# MPPT3.net
KiCad netlist of a schematic drawn in EAGLE
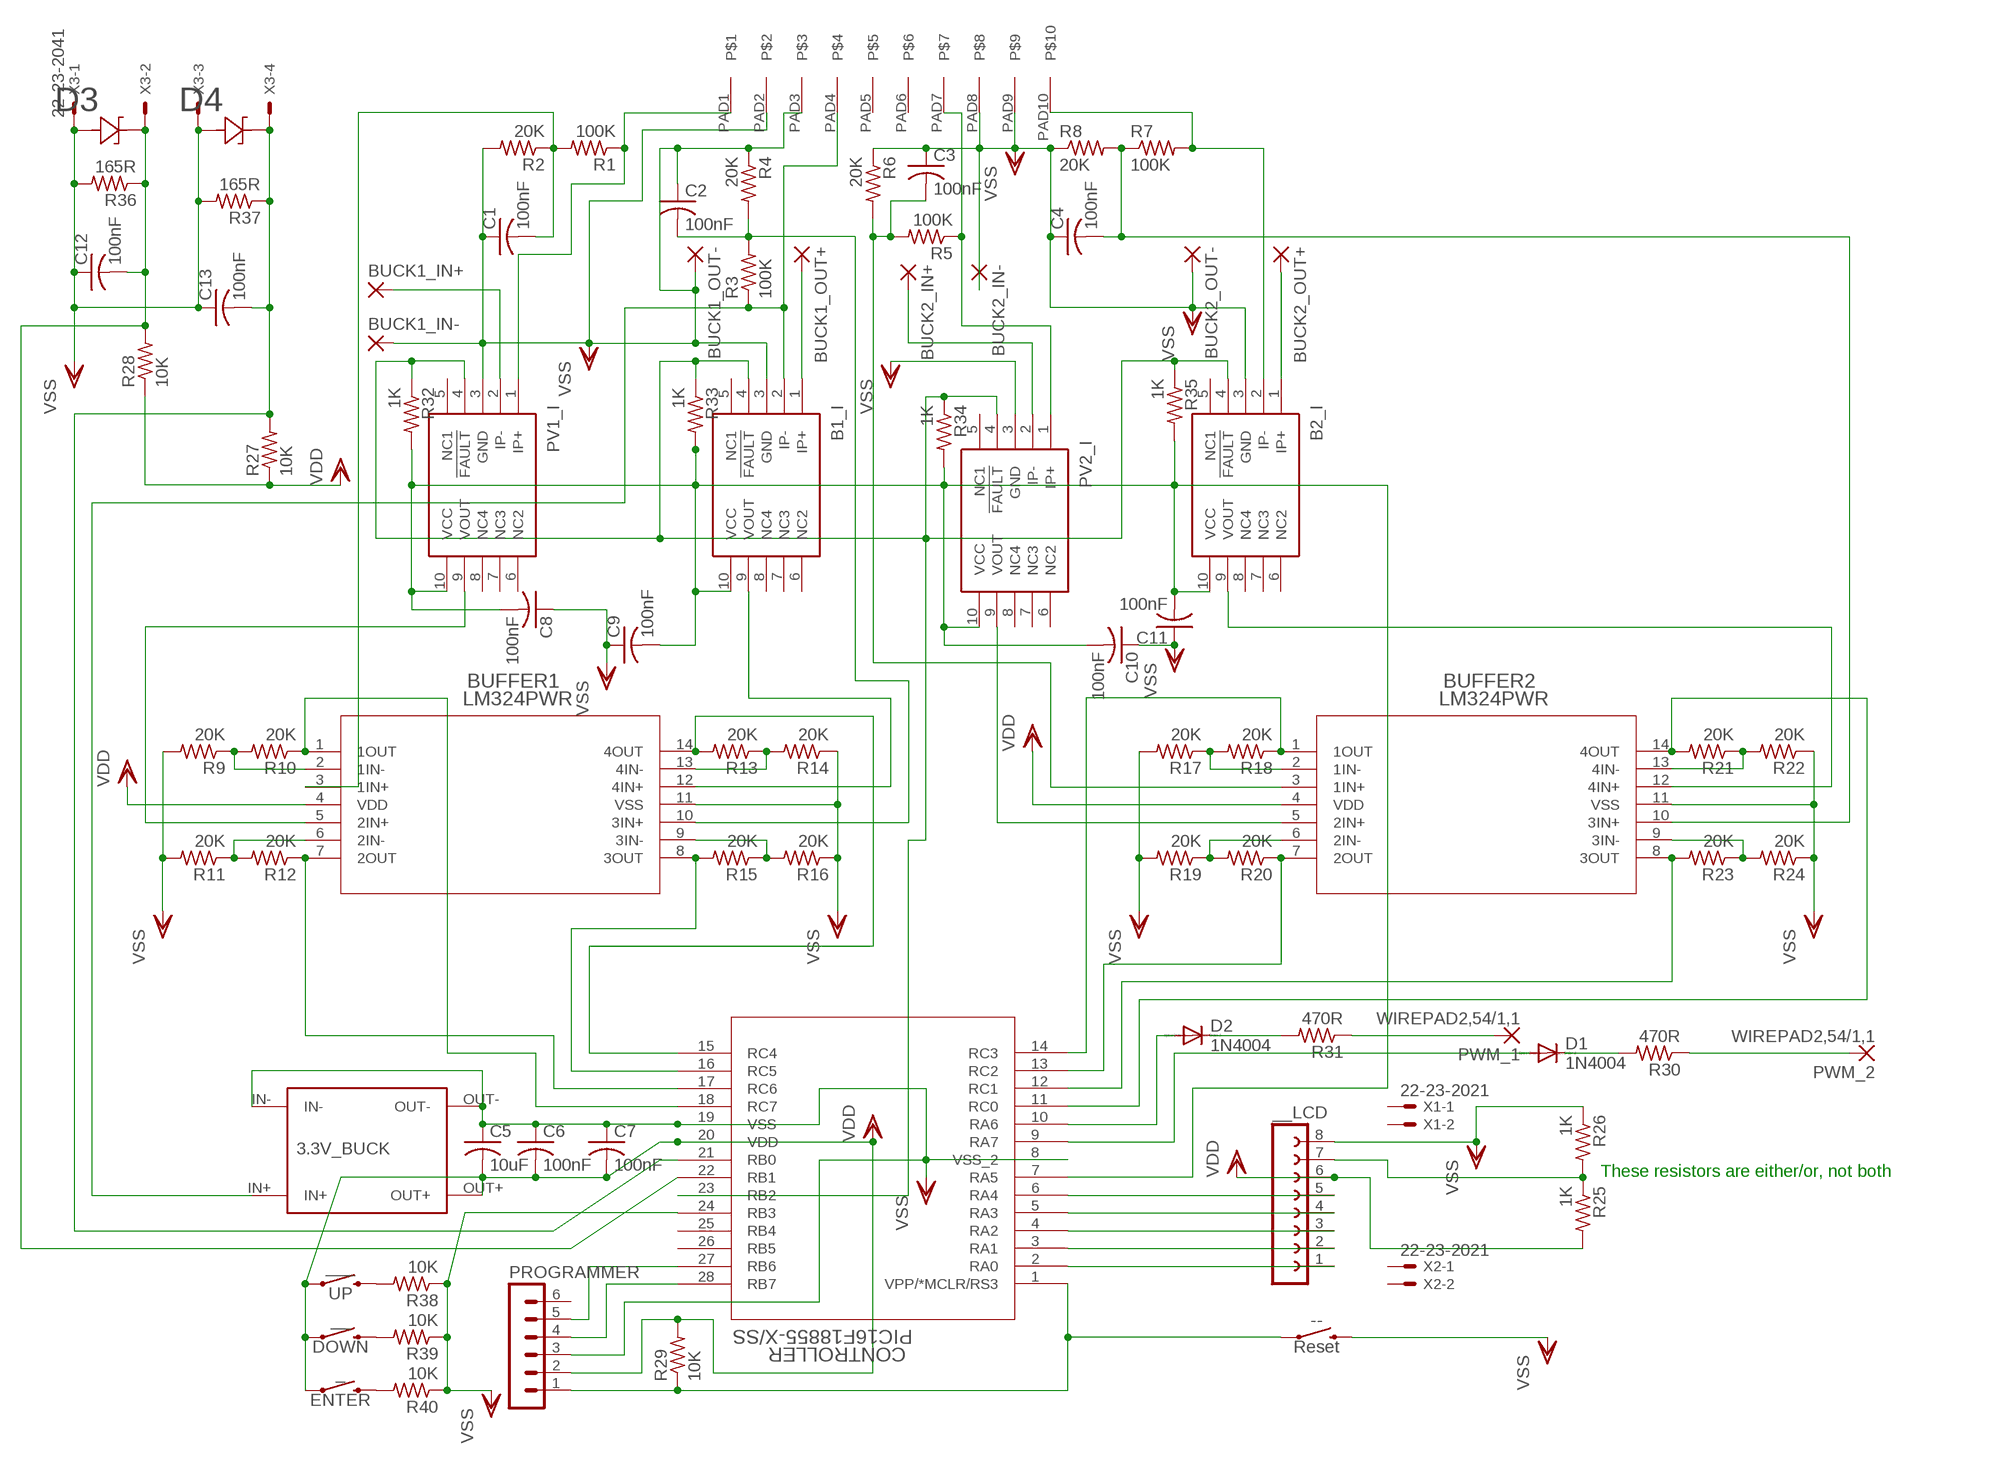
[diagram p0: schematic, sheet 1]

(export (version "E")
  (design (tool "Eeschema 10.0.6"))
  (components
    (comp (ref "--")
      (value "Reset")
      (footprint "eagle-import:TACTILE_SWITCH_PTH_6.0MM")
      (libsource (lib "eagle-import") (part "MOMENTARY-SWITCH-SPST-PTH-6.0MM"))
    )
    (comp (ref "3.3V_BUCK")
      (value "TINY_BUCK")
      (footprint "eagle-import:TINY_BUCK")
      (libsource (lib "eagle-import") (part "TINY_BUCK"))
    )
    (comp (ref "B1_I")
      (value "ACS711KEXLT-15AB-T")
      (footprint "eagle-import:EX-PACKAGE")
      (libsource (lib "eagle-import") (part "ACS711KEXLT-15AB-T"))
    )
    (comp (ref "B2_I")
      (value "ACS711KEXLT-15AB-T")
      (footprint "eagle-import:EX-PACKAGE")
      (libsource (lib "eagle-import") (part "ACS711KEXLT-15AB-T"))
    )
    (comp (ref "BUCK1_IN+")
      (value "3,81/1,4")
      (footprint "eagle-import:3,81_1,4")
      (libsource (lib "eagle-import") (part "3,81/1,4"))
    )
    (comp (ref "BUCK1_IN-")
      (value "3,81/1,4")
      (footprint "eagle-import:3,81_1,4")
      (libsource (lib "eagle-import") (part "3,81/1,4"))
    )
    (comp (ref "BUCK1_OUT+")
      (value "3,81/1,4")
      (footprint "eagle-import:3,81_1,4")
      (libsource (lib "eagle-import") (part "3,81/1,4"))
    )
    (comp (ref "BUCK1_OUT-")
      (value "3,81/1,4")
      (footprint "eagle-import:3,81_1,4")
      (libsource (lib "eagle-import") (part "3,81/1,4"))
    )
    (comp (ref "BUCK2_IN+")
      (value "3,81/1,4")
      (footprint "eagle-import:3,81_1,4")
      (libsource (lib "eagle-import") (part "3,81/1,4"))
    )
    (comp (ref "BUCK2_IN-")
      (value "3,81/1,4")
      (footprint "eagle-import:3,81_1,4")
      (libsource (lib "eagle-import") (part "3,81/1,4"))
    )
    (comp (ref "BUCK2_OUT+")
      (value "3,81/1,4")
      (footprint "eagle-import:3,81_1,4")
      (libsource (lib "eagle-import") (part "3,81/1,4"))
    )
    (comp (ref "BUCK2_OUT-")
      (value "3,81/1,4")
      (footprint "eagle-import:3,81_1,4")
      (libsource (lib "eagle-import") (part "3,81/1,4"))
    )
    (comp (ref "BUFFER1")
      (value "LM324PWR")
      (footprint "eagle-import:PW14")
      (libsource (lib "eagle-import") (part "LM324PWR"))
    )
    (comp (ref "BUFFER2")
      (value "LM324PWR")
      (footprint "eagle-import:PW14")
      (libsource (lib "eagle-import") (part "LM324PWR"))
    )
    (comp (ref "C1")
      (value "100nF")
      (footprint "eagle-import:C0603")
      (libsource (lib "eagle-import") (part "C-USC0603"))
    )
    (comp (ref "C2")
      (value "100nF")
      (footprint "eagle-import:C0603")
      (libsource (lib "eagle-import") (part "C-USC0603"))
    )
    (comp (ref "C3")
      (value "100nF")
      (footprint "eagle-import:C0603")
      (libsource (lib "eagle-import") (part "C-USC0603"))
    )
    (comp (ref "C4")
      (value "100nF")
      (footprint "eagle-import:C0603")
      (libsource (lib "eagle-import") (part "C-USC0603"))
    )
    (comp (ref "C5")
      (value "10uF")
      (footprint "eagle-import:C0603")
      (libsource (lib "eagle-import") (part "C-USC0603"))
    )
    (comp (ref "C6")
      (value "100nF")
      (footprint "eagle-import:C0603")
      (libsource (lib "eagle-import") (part "C-USC0603"))
    )
    (comp (ref "C7")
      (value "100nF")
      (footprint "eagle-import:C0603")
      (libsource (lib "eagle-import") (part "C-USC0603"))
    )
    (comp (ref "C8")
      (value "100nF")
      (footprint "eagle-import:C0603")
      (libsource (lib "eagle-import") (part "C-USC0603"))
    )
    (comp (ref "C9")
      (value "100nF")
      (footprint "eagle-import:C0603")
      (libsource (lib "eagle-import") (part "C-USC0603"))
    )
    (comp (ref "C10")
      (value "100nF")
      (footprint "eagle-import:C0603")
      (libsource (lib "eagle-import") (part "C-USC0603"))
    )
    (comp (ref "C11")
      (value "100nF")
      (footprint "eagle-import:C0603")
      (libsource (lib "eagle-import") (part "C-USC0603"))
    )
    (comp (ref "C12")
      (value "100nF")
      (footprint "eagle-import:C0603")
      (libsource (lib "eagle-import") (part "C-USC0603"))
    )
    (comp (ref "C13")
      (value "100nF")
      (footprint "eagle-import:C0603")
      (libsource (lib "eagle-import") (part "C-USC0603"))
    )
    (comp (ref "CONTROLLER")
      (value "PIC16F18855-X/SS")
      (footprint "eagle-import:SSOP28_MC")
      (fields
        (field (name "MANUFACTURER_PART_NUMBER") "pic16f18855-x/ss")
        (field (name "COPYRIGHT") "Copyright (C) 2016 Accelerated Designs. All rights reserved")
      )
      (libsource (lib "eagle-import") (part "PIC16F18855-X/SS"))
    )
    (comp (ref "D1")
      (value "1N4004")
      (footprint "eagle-import:DO41-10")
      (libsource (lib "eagle-import") (part "1N4004"))
    )
    (comp (ref "D2")
      (value "1N4004")
      (footprint "eagle-import:DO41-10")
      (libsource (lib "eagle-import") (part "1N4004"))
    )
    (comp (ref "D3")
      (value "CZRU52C3V3")
      (footprint "eagle-import:CZRU")
      (libsource (lib "eagle-import") (part "CZRU52C3V3"))
    )
    (comp (ref "D4")
      (value "CZRU52C3V3")
      (footprint "eagle-import:CZRU")
      (libsource (lib "eagle-import") (part "CZRU52C3V3"))
    )
    (comp (ref "PROGRAMMER")
      (value "MA06-1")
      (footprint "eagle-import:MA06-1")
      (libsource (lib "eagle-import") (part "MA06-1"))
    )
    (comp (ref "PV1_I")
      (value "ACS711KEXLT-15AB-T")
      (footprint "eagle-import:EX-PACKAGE")
      (libsource (lib "eagle-import") (part "ACS711KEXLT-15AB-T"))
    )
    (comp (ref "PV2_I")
      (value "ACS711KEXLT-15AB-T")
      (footprint "eagle-import:EX-PACKAGE")
      (libsource (lib "eagle-import") (part "ACS711KEXLT-15AB-T"))
    )
    (comp (ref "PWM_1")
      (value "WIREPAD2,54/1,1")
      (footprint "eagle-import:2,54_1,1")
      (libsource (lib "eagle-import") (part "WIREPAD2,54/1,1"))
    )
    (comp (ref "PWM_2")
      (value "WIREPAD2,54/1,1")
      (footprint "eagle-import:2,54_1,1")
      (libsource (lib "eagle-import") (part "WIREPAD2,54/1,1"))
    )
    (comp (ref "R1")
      (value "100K")
      (footprint "eagle-import:R0603")
      (libsource (lib "eagle-import") (part "resistor_R-US_R0603"))
    )
    (comp (ref "R2")
      (value "20K")
      (footprint "eagle-import:R0603")
      (libsource (lib "eagle-import") (part "resistor_R-US_R0603"))
    )
    (comp (ref "R3")
      (value "100K")
      (footprint "eagle-import:R0603")
      (libsource (lib "eagle-import") (part "resistor_R-US_R0603"))
    )
    (comp (ref "R4")
      (value "20K")
      (footprint "eagle-import:R0603")
      (libsource (lib "eagle-import") (part "resistor_R-US_R0603"))
    )
    (comp (ref "R5")
      (value "100K")
      (footprint "eagle-import:R1206")
      (libsource (lib "eagle-import") (part "resistor_R-US_R1206"))
    )
    (comp (ref "R6")
      (value "20K")
      (footprint "eagle-import:R0603")
      (libsource (lib "eagle-import") (part "resistor_R-US_R0603"))
    )
    (comp (ref "R7")
      (value "100K")
      (footprint "eagle-import:R0603")
      (libsource (lib "eagle-import") (part "resistor_R-US_R0603"))
    )
    (comp (ref "R8")
      (value "20K")
      (footprint "eagle-import:R0603")
      (libsource (lib "eagle-import") (part "resistor_R-US_R0603"))
    )
    (comp (ref "R9")
      (value "20K")
      (footprint "eagle-import:R0603")
      (libsource (lib "eagle-import") (part "resistor_R-US_R0603"))
    )
    (comp (ref "R10")
      (value "20K")
      (footprint "eagle-import:R0603")
      (libsource (lib "eagle-import") (part "resistor_R-US_R0603"))
    )
    (comp (ref "R11")
      (value "20K")
      (footprint "eagle-import:R0603")
      (libsource (lib "eagle-import") (part "resistor_R-US_R0603"))
    )
    (comp (ref "R12")
      (value "20K")
      (footprint "eagle-import:R0603")
      (libsource (lib "eagle-import") (part "resistor_R-US_R0603"))
    )
    (comp (ref "R13")
      (value "20K")
      (footprint "eagle-import:R0603")
      (libsource (lib "eagle-import") (part "resistor_R-US_R0603"))
    )
    (comp (ref "R14")
      (value "20K")
      (footprint "eagle-import:R0603")
      (libsource (lib "eagle-import") (part "resistor_R-US_R0603"))
    )
    (comp (ref "R15")
      (value "20K")
      (footprint "eagle-import:R0603")
      (libsource (lib "eagle-import") (part "resistor_R-US_R0603"))
    )
    (comp (ref "R16")
      (value "20K")
      (footprint "eagle-import:R0603")
      (libsource (lib "eagle-import") (part "resistor_R-US_R0603"))
    )
    (comp (ref "R17")
      (value "20K")
      (footprint "eagle-import:R0603")
      (libsource (lib "eagle-import") (part "resistor_R-US_R0603"))
    )
    (comp (ref "R18")
      (value "20K")
      (footprint "eagle-import:R0603")
      (libsource (lib "eagle-import") (part "resistor_R-US_R0603"))
    )
    (comp (ref "R19")
      (value "20K")
      (footprint "eagle-import:R0603")
      (libsource (lib "eagle-import") (part "resistor_R-US_R0603"))
    )
    (comp (ref "R20")
      (value "20K")
      (footprint "eagle-import:R0603")
      (libsource (lib "eagle-import") (part "resistor_R-US_R0603"))
    )
    (comp (ref "R21")
      (value "20K")
      (footprint "eagle-import:R0603")
      (libsource (lib "eagle-import") (part "resistor_R-US_R0603"))
    )
    (comp (ref "R22")
      (value "20K")
      (footprint "eagle-import:R0603")
      (libsource (lib "eagle-import") (part "resistor_R-US_R0603"))
    )
    (comp (ref "R23")
      (value "20K")
      (footprint "eagle-import:R0603")
      (libsource (lib "eagle-import") (part "resistor_R-US_R0603"))
    )
    (comp (ref "R24")
      (value "20K")
      (footprint "eagle-import:R0603")
      (libsource (lib "eagle-import") (part "resistor_R-US_R0603"))
    )
    (comp (ref "R25")
      (value "1K")
      (footprint "eagle-import:R0603")
      (libsource (lib "eagle-import") (part "resistor_R-US_R0603"))
    )
    (comp (ref "R26")
      (value "1K")
      (footprint "eagle-import:R0603")
      (libsource (lib "eagle-import") (part "resistor_R-US_R0603"))
    )
    (comp (ref "R27")
      (value "10K")
      (footprint "eagle-import:R1206")
      (libsource (lib "eagle-import") (part "R-US_R1206"))
    )
    (comp (ref "R28")
      (value "10K")
      (footprint "eagle-import:R0603")
      (libsource (lib "eagle-import") (part "resistor_R-US_R0603"))
    )
    (comp (ref "R29")
      (value "10K")
      (footprint "eagle-import:R0603")
      (libsource (lib "eagle-import") (part "resistor_R-US_R0603"))
    )
    (comp (ref "R30")
      (value "470R")
      (footprint "eagle-import:R0603")
      (libsource (lib "eagle-import") (part "resistor_R-US_R0603"))
    )
    (comp (ref "R31")
      (value "470R")
      (footprint "eagle-import:R1206")
      (libsource (lib "eagle-import") (part "resistor_R-US_R1206"))
    )
    (comp (ref "R32")
      (value "1K")
      (footprint "eagle-import:R1206")
      (libsource (lib "eagle-import") (part "resistor_R-US_R1206"))
    )
    (comp (ref "R33")
      (value "1K")
      (footprint "eagle-import:R1206")
      (libsource (lib "eagle-import") (part "resistor_R-US_R1206"))
    )
    (comp (ref "R34")
      (value "1K")
      (footprint "eagle-import:R0603")
      (libsource (lib "eagle-import") (part "resistor_R-US_R0603"))
    )
    (comp (ref "R35")
      (value "1K")
      (footprint "eagle-import:R0603")
      (libsource (lib "eagle-import") (part "resistor_R-US_R0603"))
    )
    (comp (ref "R36")
      (value "165R")
      (footprint "eagle-import:R0603")
      (libsource (lib "eagle-import") (part "resistor_R-US_R0603"))
    )
    (comp (ref "R37")
      (value "165R")
      (footprint "eagle-import:R0603")
      (libsource (lib "eagle-import") (part "resistor_R-US_R0603"))
    )
    (comp (ref "R38")
      (value "10K")
      (footprint "eagle-import:R0603")
      (libsource (lib "eagle-import") (part "resistor_R-US_R0603"))
    )
    (comp (ref "R39")
      (value "10K")
      (footprint "eagle-import:R0603")
      (libsource (lib "eagle-import") (part "resistor_R-US_R0603"))
    )
    (comp (ref "R40")
      (value "10K")
      (footprint "eagle-import:R0603")
      (libsource (lib "eagle-import") (part "resistor_R-US_R0603"))
    )
    (comp (ref "U$1")
      (value "CONN-KF2EDG-10(5.08)E-BAYPLUGGABLECONNECTORS")
      (footprint "eagle-import:CONN-KF2EDG-10(5.08)")
      (libsource (lib "eagle-import") (part "CONN-KF2EDG-10(5.08)E-BAYPLUGGABLECONNECTORS"))
    )
    (comp (ref "X1")
      (value "22-23-2021")
      (footprint "eagle-import:22-23-2021")
      (fields (field (name "MF") "MOLEX"))
      (libsource (lib "eagle-import") (part "22-23-2021"))
    )
    (comp (ref "X2")
      (value "22-23-2021")
      (footprint "eagle-import:22-23-2021")
      (fields (field (name "MF") "MOLEX"))
      (libsource (lib "eagle-import") (part "22-23-2021"))
    )
    (comp (ref "X3")
      (value "22-23-2041")
      (footprint "eagle-import:22-23-2041")
      (fields (field (name "MF") "MOLEX"))
      (libsource (lib "eagle-import") (part "22-23-2041"))
    )
    (comp (ref "_")
      (value "ENTER")
      (footprint "eagle-import:TACTILE_SWITCH_PTH_6.0MM")
      (libsource (lib "eagle-import") (part "MOMENTARY-SWITCH-SPST-PTH-6.0MM"))
    )
    (comp (ref "__")
      (value "DOWN")
      (footprint "eagle-import:TACTILE_SWITCH_PTH_6.0MM")
      (libsource (lib "eagle-import") (part "MOMENTARY-SWITCH-SPST-PTH-6.0MM"))
    )
    (comp (ref "__LCD")
      (value "FE08-1")
      (footprint "eagle-import:FE08")
      (libsource (lib "eagle-import") (part "FE08-1"))
    )
    (comp (ref "___")
      (value "UP")
      (footprint "eagle-import:TACTILE_SWITCH_PTH_6.0MM")
      (libsource (lib "eagle-import") (part "MOMENTARY-SWITCH-SPST-PTH-6.0MM"))
    )
  )
  (nets
    (net (code "1") (name "Net-(B1_I-IP+)") (class "Default")
      (node (ref "B1_I") (pin "1") (pinfunction "IP+_1") (pintype "bidirectional"))
      (node (ref "BUCK1_OUT+") (pin "1") (pinfunction "P_1") (pintype "passive"))
    )
    (net (code "2") (name "Net-(B1_I-IP-)") (class "Default")
      (node (ref "3.3V_BUCK") (pin "IN+") (pinfunction "IN+_IN+") (pintype "power_in"))
      (node (ref "B1_I") (pin "2") (pinfunction "IP-_2") (pintype "bidirectional"))
      (node (ref "R3") (pin "1") (pinfunction "1_1") (pintype "passive"))
      (node (ref "U$1") (pin "PAD4") (pinfunction "P$4_PAD4") (pintype "bidirectional"))
    )
    (net (code "3") (name "Net-(B1_I-VCC)") (class "Default")
      (node (ref "B1_I") (pin "10") (pinfunction "VCC_10") (pintype "bidirectional"))
      (node (ref "B2_I") (pin "10") (pinfunction "VCC_10") (pintype "bidirectional"))
      (node (ref "C10") (pin "2") (pinfunction "2_2") (pintype "passive"))
      (node (ref "C11") (pin "2") (pinfunction "2_2") (pintype "passive"))
      (node (ref "C8") (pin "2") (pinfunction "2_2") (pintype "passive"))
      (node (ref "C9") (pin "2") (pinfunction "2_2") (pintype "passive"))
      (node (ref "CONTROLLER") (pin "7") (pinfunction "RA5_7") (pintype "bidirectional"))
      (node (ref "PV1_I") (pin "10") (pinfunction "VCC_10") (pintype "bidirectional"))
      (node (ref "PV2_I") (pin "10") (pinfunction "VCC_10") (pintype "bidirectional"))
      (node (ref "R32") (pin "2") (pinfunction "2_2") (pintype "passive"))
      (node (ref "R33") (pin "2") (pinfunction "2_2") (pintype "passive"))
      (node (ref "R34") (pin "2") (pinfunction "2_2") (pintype "passive"))
      (node (ref "R35") (pin "2") (pinfunction "2_2") (pintype "passive"))
    )
    (net (code "4") (name "Net-(B1_I-VOUT)") (class "Default")
      (node (ref "B1_I") (pin "9") (pinfunction "VOUT_9") (pintype "bidirectional"))
      (node (ref "BUFFER1") (pin "12") (pinfunction "4IN+_12") (pintype "input"))
    )
    (net (code "5") (name "Net-(B1_I-~{FAULT})") (class "Default")
      (node (ref "B1_I") (pin "4") (pinfunction "~{FAULT}_4") (pintype "bidirectional"))
      (node (ref "B2_I") (pin "4") (pinfunction "~{FAULT}_4") (pintype "bidirectional"))
      (node (ref "CONTROLLER") (pin "23") (pinfunction "RB2_23") (pintype "bidirectional"))
      (node (ref "PV1_I") (pin "4") (pinfunction "~{FAULT}_4") (pintype "bidirectional"))
      (node (ref "PV2_I") (pin "4") (pinfunction "~{FAULT}_4") (pintype "bidirectional"))
      (node (ref "R32") (pin "1") (pinfunction "1_1") (pintype "passive"))
      (node (ref "R33") (pin "1") (pinfunction "1_1") (pintype "passive"))
      (node (ref "R34") (pin "1") (pinfunction "1_1") (pintype "passive"))
      (node (ref "R35") (pin "1") (pinfunction "1_1") (pintype "passive"))
    )
    (net (code "6") (name "Net-(B2_I-IP+)") (class "Default")
      (node (ref "B2_I") (pin "1") (pinfunction "IP+_1") (pintype "bidirectional"))
      (node (ref "BUCK2_OUT+") (pin "1") (pinfunction "P_1") (pintype "passive"))
    )
    (net (code "7") (name "Net-(B2_I-IP-)") (class "Default")
      (node (ref "B2_I") (pin "2") (pinfunction "IP-_2") (pintype "bidirectional"))
      (node (ref "R7") (pin "2") (pinfunction "2_2") (pintype "passive"))
      (node (ref "U$1") (pin "PAD10") (pinfunction "P$10_PAD10") (pintype "bidirectional"))
    )
    (net (code "8") (name "Net-(B2_I-VOUT)") (class "Default")
      (node (ref "B2_I") (pin "9") (pinfunction "VOUT_9") (pintype "bidirectional"))
      (node (ref "BUFFER2") (pin "12") (pinfunction "4IN+_12") (pintype "input"))
    )
    (net (code "9") (name "Net-(BUCK1_IN+-P)") (class "Default")
      (node (ref "BUCK1_IN+") (pin "1") (pinfunction "P_1") (pintype "passive"))
      (node (ref "PV1_I") (pin "2") (pinfunction "IP-_2") (pintype "bidirectional"))
    )
    (net (code "10") (name "Net-(BUCK2_IN+-P)") (class "Default")
      (node (ref "BUCK2_IN+") (pin "1") (pinfunction "P_1") (pintype "passive"))
      (node (ref "PV2_I") (pin "2") (pinfunction "IP-_2") (pintype "bidirectional"))
    )
    (net (code "11") (name "Net-(BUFFER1-1IN+)") (class "Default")
      (node (ref "BUFFER1") (pin "3") (pinfunction "1IN+_3") (pintype "input"))
      (node (ref "C1") (pin "2") (pinfunction "2_2") (pintype "passive"))
      (node (ref "R1") (pin "2") (pinfunction "2_2") (pintype "passive"))
      (node (ref "R2") (pin "1") (pinfunction "1_1") (pintype "passive"))
    )
    (net (code "12") (name "Net-(BUFFER1-1IN-)") (class "Default")
      (node (ref "BUFFER1") (pin "2") (pinfunction "1IN-_2") (pintype "input"))
      (node (ref "R10") (pin "2") (pinfunction "2_2") (pintype "passive"))
      (node (ref "R9") (pin "1") (pinfunction "1_1") (pintype "passive"))
    )
    (net (code "13") (name "Net-(BUFFER1-1OUT)") (class "Default")
      (node (ref "BUFFER1") (pin "1") (pinfunction "1OUT_1") (pintype "output"))
      (node (ref "CONTROLLER") (pin "18") (pinfunction "RC7_18") (pintype "bidirectional"))
      (node (ref "R10") (pin "1") (pinfunction "1_1") (pintype "passive"))
    )
    (net (code "14") (name "Net-(BUFFER1-2IN+)") (class "Default")
      (node (ref "BUFFER1") (pin "5") (pinfunction "2IN+_5") (pintype "input"))
      (node (ref "PV1_I") (pin "9") (pinfunction "VOUT_9") (pintype "bidirectional"))
    )
    (net (code "15") (name "Net-(BUFFER1-2IN-)") (class "Default")
      (node (ref "BUFFER1") (pin "6") (pinfunction "2IN-_6") (pintype "input"))
      (node (ref "R11") (pin "1") (pinfunction "1_1") (pintype "passive"))
      (node (ref "R12") (pin "2") (pinfunction "2_2") (pintype "passive"))
    )
    (net (code "16") (name "Net-(BUFFER1-2OUT)") (class "Default")
      (node (ref "BUFFER1") (pin "7") (pinfunction "2OUT_7") (pintype "output"))
      (node (ref "CONTROLLER") (pin "17") (pinfunction "RC6_17") (pintype "bidirectional"))
      (node (ref "R12") (pin "1") (pinfunction "1_1") (pintype "passive"))
    )
    (net (code "17") (name "Net-(BUFFER1-3IN+)") (class "Default")
      (node (ref "BUFFER1") (pin "10") (pinfunction "3IN+_10") (pintype "input"))
      (node (ref "C2") (pin "2") (pinfunction "2_2") (pintype "passive"))
      (node (ref "R3") (pin "2") (pinfunction "2_2") (pintype "passive"))
      (node (ref "R4") (pin "2") (pinfunction "2_2") (pintype "passive"))
    )
    (net (code "18") (name "Net-(BUFFER1-3IN-)") (class "Default")
      (node (ref "BUFFER1") (pin "9") (pinfunction "3IN-_9") (pintype "input"))
      (node (ref "R15") (pin "1") (pinfunction "1_1") (pintype "passive"))
      (node (ref "R16") (pin "2") (pinfunction "2_2") (pintype "passive"))
    )
    (net (code "19") (name "Net-(BUFFER1-3OUT)") (class "Default")
      (node (ref "BUFFER1") (pin "8") (pinfunction "3OUT_8") (pintype "output"))
      (node (ref "CONTROLLER") (pin "16") (pinfunction "RC5_16") (pintype "bidirectional"))
      (node (ref "R15") (pin "2") (pinfunction "2_2") (pintype "passive"))
    )
    (net (code "20") (name "Net-(BUFFER1-4IN-)") (class "Default")
      (node (ref "BUFFER1") (pin "13") (pinfunction "4IN-_13") (pintype "input"))
      (node (ref "R13") (pin "1") (pinfunction "1_1") (pintype "passive"))
      (node (ref "R14") (pin "2") (pinfunction "2_2") (pintype "passive"))
    )
    (net (code "21") (name "Net-(BUFFER1-4OUT)") (class "Default")
      (node (ref "BUFFER1") (pin "14") (pinfunction "4OUT_14") (pintype "output"))
      (node (ref "CONTROLLER") (pin "15") (pinfunction "RC4_15") (pintype "bidirectional"))
      (node (ref "R13") (pin "2") (pinfunction "2_2") (pintype "passive"))
    )
    (net (code "22") (name "Net-(BUFFER2-1IN+)") (class "Default")
      (node (ref "BUFFER2") (pin "3") (pinfunction "1IN+_3") (pintype "input"))
      (node (ref "C3") (pin "2") (pinfunction "2_2") (pintype "passive"))
      (node (ref "R5") (pin "2") (pinfunction "2_2") (pintype "passive"))
      (node (ref "R6") (pin "2") (pinfunction "2_2") (pintype "passive"))
    )
    (net (code "23") (name "Net-(BUFFER2-1IN-)") (class "Default")
      (node (ref "BUFFER2") (pin "2") (pinfunction "1IN-_2") (pintype "input"))
      (node (ref "R17") (pin "1") (pinfunction "1_1") (pintype "passive"))
      (node (ref "R18") (pin "2") (pinfunction "2_2") (pintype "passive"))
    )
    (net (code "24") (name "Net-(BUFFER2-1OUT)") (class "Default")
      (node (ref "BUFFER2") (pin "1") (pinfunction "1OUT_1") (pintype "output"))
      (node (ref "CONTROLLER") (pin "14") (pinfunction "RC3_14") (pintype "bidirectional"))
      (node (ref "R18") (pin "1") (pinfunction "1_1") (pintype "passive"))
    )
    (net (code "25") (name "Net-(BUFFER2-2IN+)") (class "Default")
      (node (ref "BUFFER2") (pin "5") (pinfunction "2IN+_5") (pintype "input"))
      (node (ref "PV2_I") (pin "9") (pinfunction "VOUT_9") (pintype "bidirectional"))
    )
    (net (code "26") (name "Net-(BUFFER2-2IN-)") (class "Default")
      (node (ref "BUFFER2") (pin "6") (pinfunction "2IN-_6") (pintype "input"))
      (node (ref "R19") (pin "1") (pinfunction "1_1") (pintype "passive"))
      (node (ref "R20") (pin "2") (pinfunction "2_2") (pintype "passive"))
    )
    (net (code "27") (name "Net-(BUFFER2-2OUT)") (class "Default")
      (node (ref "BUFFER2") (pin "7") (pinfunction "2OUT_7") (pintype "output"))
      (node (ref "CONTROLLER") (pin "13") (pinfunction "RC2_13") (pintype "bidirectional"))
      (node (ref "R20") (pin "1") (pinfunction "1_1") (pintype "passive"))
    )
    (net (code "28") (name "Net-(BUFFER2-3IN+)") (class "Default")
      (node (ref "BUFFER2") (pin "10") (pinfunction "3IN+_10") (pintype "input"))
      (node (ref "C4") (pin "2") (pinfunction "2_2") (pintype "passive"))
      (node (ref "R7") (pin "1") (pinfunction "1_1") (pintype "passive"))
      (node (ref "R8") (pin "2") (pinfunction "2_2") (pintype "passive"))
    )
    (net (code "29") (name "Net-(BUFFER2-3IN-)") (class "Default")
      (node (ref "BUFFER2") (pin "9") (pinfunction "3IN-_9") (pintype "input"))
      (node (ref "R23") (pin "1") (pinfunction "1_1") (pintype "passive"))
      (node (ref "R24") (pin "2") (pinfunction "2_2") (pintype "passive"))
    )
    (net (code "30") (name "Net-(BUFFER2-3OUT)") (class "Default")
      (node (ref "BUFFER2") (pin "8") (pinfunction "3OUT_8") (pintype "output"))
      (node (ref "CONTROLLER") (pin "12") (pinfunction "RC1_12") (pintype "bidirectional"))
      (node (ref "R23") (pin "2") (pinfunction "2_2") (pintype "passive"))
    )
    (net (code "31") (name "Net-(BUFFER2-4IN-)") (class "Default")
      (node (ref "BUFFER2") (pin "13") (pinfunction "4IN-_13") (pintype "input"))
      (node (ref "R21") (pin "1") (pinfunction "1_1") (pintype "passive"))
      (node (ref "R22") (pin "2") (pinfunction "2_2") (pintype "passive"))
    )
    (net (code "32") (name "Net-(BUFFER2-4OUT)") (class "Default")
      (node (ref "BUFFER2") (pin "14") (pinfunction "4OUT_14") (pintype "output"))
      (node (ref "CONTROLLER") (pin "11") (pinfunction "RC0_11") (pintype "bidirectional"))
      (node (ref "R21") (pin "2") (pinfunction "2_2") (pintype "passive"))
    )
    (net (code "33") (name "Net-(CONTROLLER-RA0)") (class "Default")
      (node (ref "CONTROLLER") (pin "2") (pinfunction "RA0_2") (pintype "bidirectional"))
      (node (ref "__LCD") (pin "1") (pinfunction "1_1") (pintype "passive"))
    )
    (net (code "34") (name "Net-(CONTROLLER-RA1)") (class "Default")
      (node (ref "CONTROLLER") (pin "3") (pinfunction "RA1_3") (pintype "bidirectional"))
      (node (ref "__LCD") (pin "2") (pinfunction "2_2") (pintype "passive"))
    )
    (net (code "35") (name "Net-(CONTROLLER-RA2)") (class "Default")
      (node (ref "CONTROLLER") (pin "4") (pinfunction "RA2_4") (pintype "bidirectional"))
      (node (ref "__LCD") (pin "3") (pinfunction "3_3") (pintype "passive"))
    )
    (net (code "36") (name "Net-(CONTROLLER-RA3)") (class "Default")
      (node (ref "CONTROLLER") (pin "5") (pinfunction "RA3_5") (pintype "bidirectional"))
      (node (ref "__LCD") (pin "4") (pinfunction "4_4") (pintype "passive"))
    )
    (net (code "37") (name "Net-(CONTROLLER-RA4)") (class "Default")
      (node (ref "CONTROLLER") (pin "6") (pinfunction "RA4_6") (pintype "bidirectional"))
      (node (ref "__LCD") (pin "5") (pinfunction "5_5") (pintype "passive"))
    )
    (net (code "38") (name "Net-(CONTROLLER-RA6)") (class "Default")
      (node (ref "CONTROLLER") (pin "10") (pinfunction "RA6_10") (pintype "bidirectional"))
      (node (ref "D2") (pin "A") (pinfunction "A_A") (pintype "passive"))
    )
    (net (code "39") (name "Net-(CONTROLLER-RA7)") (class "Default")
      (node (ref "CONTROLLER") (pin "9") (pinfunction "RA7_9") (pintype "bidirectional"))
      (node (ref "D1") (pin "A") (pinfunction "A_A") (pintype "passive"))
    )
    (net (code "40") (name "Net-(CONTROLLER-RB0)") (class "Default")
      (node (ref "C13") (pin "2") (pinfunction "2_2") (pintype "passive"))
      (node (ref "CONTROLLER") (pin "21") (pinfunction "RB0_21") (pintype "bidirectional"))
      (node (ref "D4") (pin "1") (pinfunction "11_1") (pintype "passive"))
      (node (ref "R27") (pin "2") (pinfunction "2_2") (pintype "passive"))
      (node (ref "R37") (pin "1") (pinfunction "1_1") (pintype "passive"))
      (node (ref "X3") (pin "4") (pinfunction "S_4") (pintype "passive"))
    )
    (net (code "41") (name "Net-(CONTROLLER-RB1)") (class "Default")
      (node (ref "C12") (pin "2") (pinfunction "2_2") (pintype "passive"))
      (node (ref "CONTROLLER") (pin "22") (pinfunction "RB1_22") (pintype "bidirectional"))
      (node (ref "D3") (pin "1") (pinfunction "11_1") (pintype "passive"))
      (node (ref "R28") (pin "2") (pinfunction "2_2") (pintype "passive"))
      (node (ref "R36") (pin "1") (pinfunction "1_1") (pintype "passive"))
      (node (ref "X3") (pin "2") (pinfunction "S_2") (pintype "passive"))
    )
    (net (code "42") (name "Net-(CONTROLLER-RB6)") (class "Default")
      (node (ref "CONTROLLER") (pin "27") (pinfunction "RB6_27") (pintype "bidirectional"))
      (node (ref "PROGRAMMER") (pin "5") (pinfunction "5_5") (pintype "passive"))
    )
    (net (code "43") (name "Net-(CONTROLLER-RB7)") (class "Default")
      (node (ref "CONTROLLER") (pin "28") (pinfunction "RB7_28") (pintype "bidirectional"))
      (node (ref "PROGRAMMER") (pin "4") (pinfunction "4_4") (pintype "passive"))
    )
    (net (code "44") (name "Net-(CONTROLLER-VPP{slash}*MCLR{slash}RS3)") (class "Default")
      (node (ref "--") (pin "1") (pinfunction "1_1") (pintype "passive"))
      (node (ref "CONTROLLER") (pin "1") (pinfunction "VPP/*MCLR/RS3_1") (pintype "bidirectional"))
      (node (ref "PROGRAMMER") (pin "1") (pinfunction "1_1") (pintype "passive"))
      (node (ref "R29") (pin "1") (pinfunction "1_1") (pintype "passive"))
    )
    (net (code "45") (name "Net-(D1-PadC)") (class "Default")
      (node (ref "D1") (pin "C") (pinfunction "C_C") (pintype "passive"))
      (node (ref "R30") (pin "2") (pinfunction "2_2") (pintype "passive"))
    )
    (net (code "46") (name "Net-(D2-PadC)") (class "Default")
      (node (ref "D2") (pin "C") (pinfunction "C_C") (pintype "passive"))
      (node (ref "R31") (pin "2") (pinfunction "2_2") (pintype "passive"))
    )
    (net (code "47") (name "Net-(PV1_I-IP+)") (class "Default")
      (node (ref "PV1_I") (pin "1") (pinfunction "IP+_1") (pintype "bidirectional"))
      (node (ref "R1") (pin "1") (pinfunction "1_1") (pintype "passive"))
      (node (ref "U$1") (pin "PAD1") (pinfunction "P$1_PAD1") (pintype "bidirectional"))
    )
    (net (code "48") (name "Net-(PV2_I-IP+)") (class "Default")
      (node (ref "PV2_I") (pin "1") (pinfunction "IP+_1") (pintype "bidirectional"))
      (node (ref "R5") (pin "1") (pinfunction "1_1") (pintype "passive"))
      (node (ref "U$1") (pin "PAD7") (pinfunction "P$7_PAD7") (pintype "bidirectional"))
    )
    (net (code "49") (name "Net-(PWM_1-P)") (class "Default")
      (node (ref "PWM_1") (pin "1") (pinfunction "P_1") (pintype "passive"))
      (node (ref "R31") (pin "1") (pinfunction "1_1") (pintype "passive"))
    )
    (net (code "50") (name "Net-(PWM_2-P)") (class "Default")
      (node (ref "PWM_2") (pin "1") (pinfunction "P_1") (pintype "passive"))
      (node (ref "R30") (pin "1") (pinfunction "1_1") (pintype "passive"))
    )
    (net (code "51") (name "Net-(R25-Pad1)") (class "Default")
      (node (ref "R25") (pin "1") (pinfunction "1_1") (pintype "passive"))
      (node (ref "R26") (pin "2") (pinfunction "2_2") (pintype "passive"))
      (node (ref "__LCD") (pin "7") (pinfunction "7_7") (pintype "passive"))
    )
    (net (code "52") (name "Net-(_-2)") (class "Default")
      (node (ref "R40") (pin "2") (pinfunction "2_2") (pintype "passive"))
      (node (ref "_") (pin "3") (pinfunction "2_3") (pintype "passive"))
    )
    (net (code "53") (name "Net-(__-2)") (class "Default")
      (node (ref "R39") (pin "2") (pinfunction "2_2") (pintype "passive"))
      (node (ref "__") (pin "3") (pinfunction "2_3") (pintype "passive"))
    )
    (net (code "54") (name "Net-(___-2)") (class "Default")
      (node (ref "R38") (pin "2") (pinfunction "2_2") (pintype "passive"))
      (node (ref "___") (pin "3") (pinfunction "2_3") (pintype "passive"))
    )
    (net (code "55") (name "VDD") (class "Default")
      (node (ref "3.3V_BUCK") (pin "OUT+") (pinfunction "OUT+_OUT+") (pintype "power_in"))
      (node (ref "BUFFER1") (pin "4") (pinfunction "VDD_4") (pintype "power_in"))
      (node (ref "BUFFER2") (pin "4") (pinfunction "VDD_4") (pintype "power_in"))
      (node (ref "C5") (pin "2") (pinfunction "2_2") (pintype "passive"))
      (node (ref "C6") (pin "2") (pinfunction "2_2") (pintype "passive"))
      (node (ref "C7") (pin "2") (pinfunction "2_2") (pintype "passive"))
      (node (ref "CONTROLLER") (pin "20") (pinfunction "VDD_20") (pintype "power_in"))
      (node (ref "PROGRAMMER") (pin "2") (pinfunction "2_2") (pintype "passive"))
      (node (ref "R25") (pin "2") (pinfunction "2_2") (pintype "passive"))
      (node (ref "R27") (pin "1") (pinfunction "1_1") (pintype "passive"))
      (node (ref "R28") (pin "1") (pinfunction "1_1") (pintype "passive"))
      (node (ref "R29") (pin "2") (pinfunction "2_2") (pintype "passive"))
      (node (ref "_") (pin "1") (pinfunction "1_1") (pintype "passive"))
      (node (ref "__") (pin "1") (pinfunction "1_1") (pintype "passive"))
      (node (ref "__LCD") (pin "6") (pinfunction "6_6") (pintype "passive"))
      (node (ref "___") (pin "1") (pinfunction "1_1") (pintype "passive"))
    )
    (net (code "56") (name "VSS") (class "Default")
      (node (ref "--") (pin "3") (pinfunction "2_3") (pintype "passive"))
      (node (ref "3.3V_BUCK") (pin "IN-") (pinfunction "IN-_IN-") (pintype "power_in"))
      (node (ref "3.3V_BUCK") (pin "OUT-") (pinfunction "OUT-_OUT-") (pintype "power_in"))
      (node (ref "B1_I") (pin "3") (pinfunction "GND_3") (pintype "bidirectional"))
      (node (ref "B2_I") (pin "3") (pinfunction "GND_3") (pintype "bidirectional"))
      (node (ref "BUCK1_IN-") (pin "1") (pinfunction "P_1") (pintype "passive"))
      (node (ref "BUCK1_OUT-") (pin "1") (pinfunction "P_1") (pintype "passive"))
      (node (ref "BUCK2_IN-") (pin "1") (pinfunction "P_1") (pintype "passive"))
      (node (ref "BUCK2_OUT-") (pin "1") (pinfunction "P_1") (pintype "passive"))
      (node (ref "BUFFER1") (pin "11") (pinfunction "VSS_11") (pintype "power_in"))
      (node (ref "BUFFER2") (pin "11") (pinfunction "VSS_11") (pintype "power_in"))
      (node (ref "C1") (pin "1") (pinfunction "1_1") (pintype "passive"))
      (node (ref "C10") (pin "1") (pinfunction "1_1") (pintype "passive"))
      (node (ref "C11") (pin "1") (pinfunction "1_1") (pintype "passive"))
      (node (ref "C12") (pin "1") (pinfunction "1_1") (pintype "passive"))
      (node (ref "C13") (pin "1") (pinfunction "1_1") (pintype "passive"))
      (node (ref "C2") (pin "1") (pinfunction "1_1") (pintype "passive"))
      (node (ref "C3") (pin "1") (pinfunction "1_1") (pintype "passive"))
      (node (ref "C4") (pin "1") (pinfunction "1_1") (pintype "passive"))
      (node (ref "C5") (pin "1") (pinfunction "1_1") (pintype "passive"))
      (node (ref "C6") (pin "1") (pinfunction "1_1") (pintype "passive"))
      (node (ref "C7") (pin "1") (pinfunction "1_1") (pintype "passive"))
      (node (ref "C8") (pin "1") (pinfunction "1_1") (pintype "passive"))
      (node (ref "C9") (pin "1") (pinfunction "1_1") (pintype "passive"))
      (node (ref "CONTROLLER") (pin "19") (pinfunction "VSS_19") (pintype "power_in"))
      (node (ref "CONTROLLER") (pin "24") (pinfunction "RB3_24") (pintype "bidirectional"))
      (node (ref "CONTROLLER") (pin "8") (pinfunction "VSS_2_8") (pintype "power_in"))
      (node (ref "D3") (pin "2") (pinfunction "22_2") (pintype "passive"))
      (node (ref "D4") (pin "2") (pinfunction "22_2") (pintype "passive"))
      (node (ref "PROGRAMMER") (pin "3") (pinfunction "3_3") (pintype "passive"))
      (node (ref "PV1_I") (pin "3") (pinfunction "GND_3") (pintype "bidirectional"))
      (node (ref "PV2_I") (pin "3") (pinfunction "GND_3") (pintype "bidirectional"))
      (node (ref "R11") (pin "2") (pinfunction "2_2") (pintype "passive"))
      (node (ref "R14") (pin "1") (pinfunction "1_1") (pintype "passive"))
      (node (ref "R16") (pin "1") (pinfunction "1_1") (pintype "passive"))
      (node (ref "R17") (pin "2") (pinfunction "2_2") (pintype "passive"))
      (node (ref "R19") (pin "2") (pinfunction "2_2") (pintype "passive"))
      (node (ref "R2") (pin "2") (pinfunction "2_2") (pintype "passive"))
      (node (ref "R22") (pin "1") (pinfunction "1_1") (pintype "passive"))
      (node (ref "R24") (pin "1") (pinfunction "1_1") (pintype "passive"))
      (node (ref "R26") (pin "1") (pinfunction "1_1") (pintype "passive"))
      (node (ref "R36") (pin "2") (pinfunction "2_2") (pintype "passive"))
      (node (ref "R37") (pin "2") (pinfunction "2_2") (pintype "passive"))
      (node (ref "R38") (pin "1") (pinfunction "1_1") (pintype "passive"))
      (node (ref "R39") (pin "1") (pinfunction "1_1") (pintype "passive"))
      (node (ref "R4") (pin "1") (pinfunction "1_1") (pintype "passive"))
      (node (ref "R40") (pin "1") (pinfunction "1_1") (pintype "passive"))
      (node (ref "R6") (pin "1") (pinfunction "1_1") (pintype "passive"))
      (node (ref "R8") (pin "1") (pinfunction "1_1") (pintype "passive"))
      (node (ref "R9") (pin "2") (pinfunction "2_2") (pintype "passive"))
      (node (ref "U$1") (pin "PAD2") (pinfunction "P$2_PAD2") (pintype "bidirectional"))
      (node (ref "U$1") (pin "PAD3") (pinfunction "P$3_PAD3") (pintype "bidirectional"))
      (node (ref "U$1") (pin "PAD8") (pinfunction "P$8_PAD8") (pintype "bidirectional"))
      (node (ref "U$1") (pin "PAD9") (pinfunction "P$9_PAD9") (pintype "bidirectional"))
      (node (ref "X3") (pin "1") (pinfunction "S_1") (pintype "passive"))
      (node (ref "X3") (pin "3") (pinfunction "S_3") (pintype "passive"))
      (node (ref "__LCD") (pin "8") (pinfunction "8_8") (pintype "passive"))
    )
    (net (code "57") (name "unconnected-(B1_I-NC1-Pad5)") (class "Default")
      (node (ref "B1_I") (pin "5") (pinfunction "NC1_5") (pintype "bidirectional"))
    )
    (net (code "58") (name "unconnected-(B1_I-NC2-Pad6)") (class "Default")
      (node (ref "B1_I") (pin "6") (pinfunction "NC2_6") (pintype "bidirectional"))
    )
    (net (code "59") (name "unconnected-(B1_I-NC3-Pad7)") (class "Default")
      (node (ref "B1_I") (pin "7") (pinfunction "NC3_7") (pintype "bidirectional"))
    )
    (net (code "60") (name "unconnected-(B1_I-NC4-Pad8)") (class "Default")
      (node (ref "B1_I") (pin "8") (pinfunction "NC4_8") (pintype "bidirectional"))
    )
    (net (code "61") (name "unconnected-(B2_I-NC1-Pad5)") (class "Default")
      (node (ref "B2_I") (pin "5") (pinfunction "NC1_5") (pintype "bidirectional"))
    )
    (net (code "62") (name "unconnected-(B2_I-NC2-Pad6)") (class "Default")
      (node (ref "B2_I") (pin "6") (pinfunction "NC2_6") (pintype "bidirectional"))
    )
    (net (code "63") (name "unconnected-(B2_I-NC3-Pad7)") (class "Default")
      (node (ref "B2_I") (pin "7") (pinfunction "NC3_7") (pintype "bidirectional"))
    )
    (net (code "64") (name "unconnected-(B2_I-NC4-Pad8)") (class "Default")
      (node (ref "B2_I") (pin "8") (pinfunction "NC4_8") (pintype "bidirectional"))
    )
    (net (code "65") (name "unconnected-(CONTROLLER-RB4-Pad25)") (class "Default")
      (node (ref "CONTROLLER") (pin "25") (pinfunction "RB4_25") (pintype "bidirectional"))
    )
    (net (code "66") (name "unconnected-(CONTROLLER-RB5-Pad26)") (class "Default")
      (node (ref "CONTROLLER") (pin "26") (pinfunction "RB5_26") (pintype "bidirectional"))
    )
    (net (code "67") (name "unconnected-(PROGRAMMER-Pad6)") (class "Default")
      (node (ref "PROGRAMMER") (pin "6") (pinfunction "6_6") (pintype "passive"))
    )
    (net (code "68") (name "unconnected-(PV1_I-NC1-Pad5)") (class "Default")
      (node (ref "PV1_I") (pin "5") (pinfunction "NC1_5") (pintype "bidirectional"))
    )
    (net (code "69") (name "unconnected-(PV1_I-NC2-Pad6)") (class "Default")
      (node (ref "PV1_I") (pin "6") (pinfunction "NC2_6") (pintype "bidirectional"))
    )
    (net (code "70") (name "unconnected-(PV1_I-NC3-Pad7)") (class "Default")
      (node (ref "PV1_I") (pin "7") (pinfunction "NC3_7") (pintype "bidirectional"))
    )
    (net (code "71") (name "unconnected-(PV1_I-NC4-Pad8)") (class "Default")
      (node (ref "PV1_I") (pin "8") (pinfunction "NC4_8") (pintype "bidirectional"))
    )
    (net (code "72") (name "unconnected-(PV2_I-NC1-Pad5)") (class "Default")
      (node (ref "PV2_I") (pin "5") (pinfunction "NC1_5") (pintype "bidirectional"))
    )
    (net (code "73") (name "unconnected-(PV2_I-NC2-Pad6)") (class "Default")
      (node (ref "PV2_I") (pin "6") (pinfunction "NC2_6") (pintype "bidirectional"))
    )
    (net (code "74") (name "unconnected-(PV2_I-NC3-Pad7)") (class "Default")
      (node (ref "PV2_I") (pin "7") (pinfunction "NC3_7") (pintype "bidirectional"))
    )
    (net (code "75") (name "unconnected-(PV2_I-NC4-Pad8)") (class "Default")
      (node (ref "PV2_I") (pin "8") (pinfunction "NC4_8") (pintype "bidirectional"))
    )
    (net (code "76") (name "unconnected-(U$1-P$5-PadPAD5)") (class "Default")
      (node (ref "U$1") (pin "PAD5") (pinfunction "P$5_PAD5") (pintype "bidirectional"))
    )
    (net (code "77") (name "unconnected-(U$1-P$6-PadPAD6)") (class "Default")
      (node (ref "U$1") (pin "PAD6") (pinfunction "P$6_PAD6") (pintype "bidirectional"))
    )
    (net (code "78") (name "unconnected-(X1A-S-Pad1)") (class "Default")
      (node (ref "X1") (pin "1") (pinfunction "S_1") (pintype "passive"))
    )
    (net (code "79") (name "unconnected-(X1B-S-Pad2)") (class "Default")
      (node (ref "X1") (pin "2") (pinfunction "S_2") (pintype "passive"))
    )
    (net (code "80") (name "unconnected-(X2A-S-Pad1)") (class "Default")
      (node (ref "X2") (pin "1") (pinfunction "S_1") (pintype "passive"))
    )
    (net (code "81") (name "unconnected-(X2B-S-Pad2)") (class "Default")
      (node (ref "X2") (pin "2") (pinfunction "S_2") (pintype "passive"))
    )
  )
)
